# analog_inputs_not_isolated.net
KiCad netlist of a schematic drawn in Altium Designer
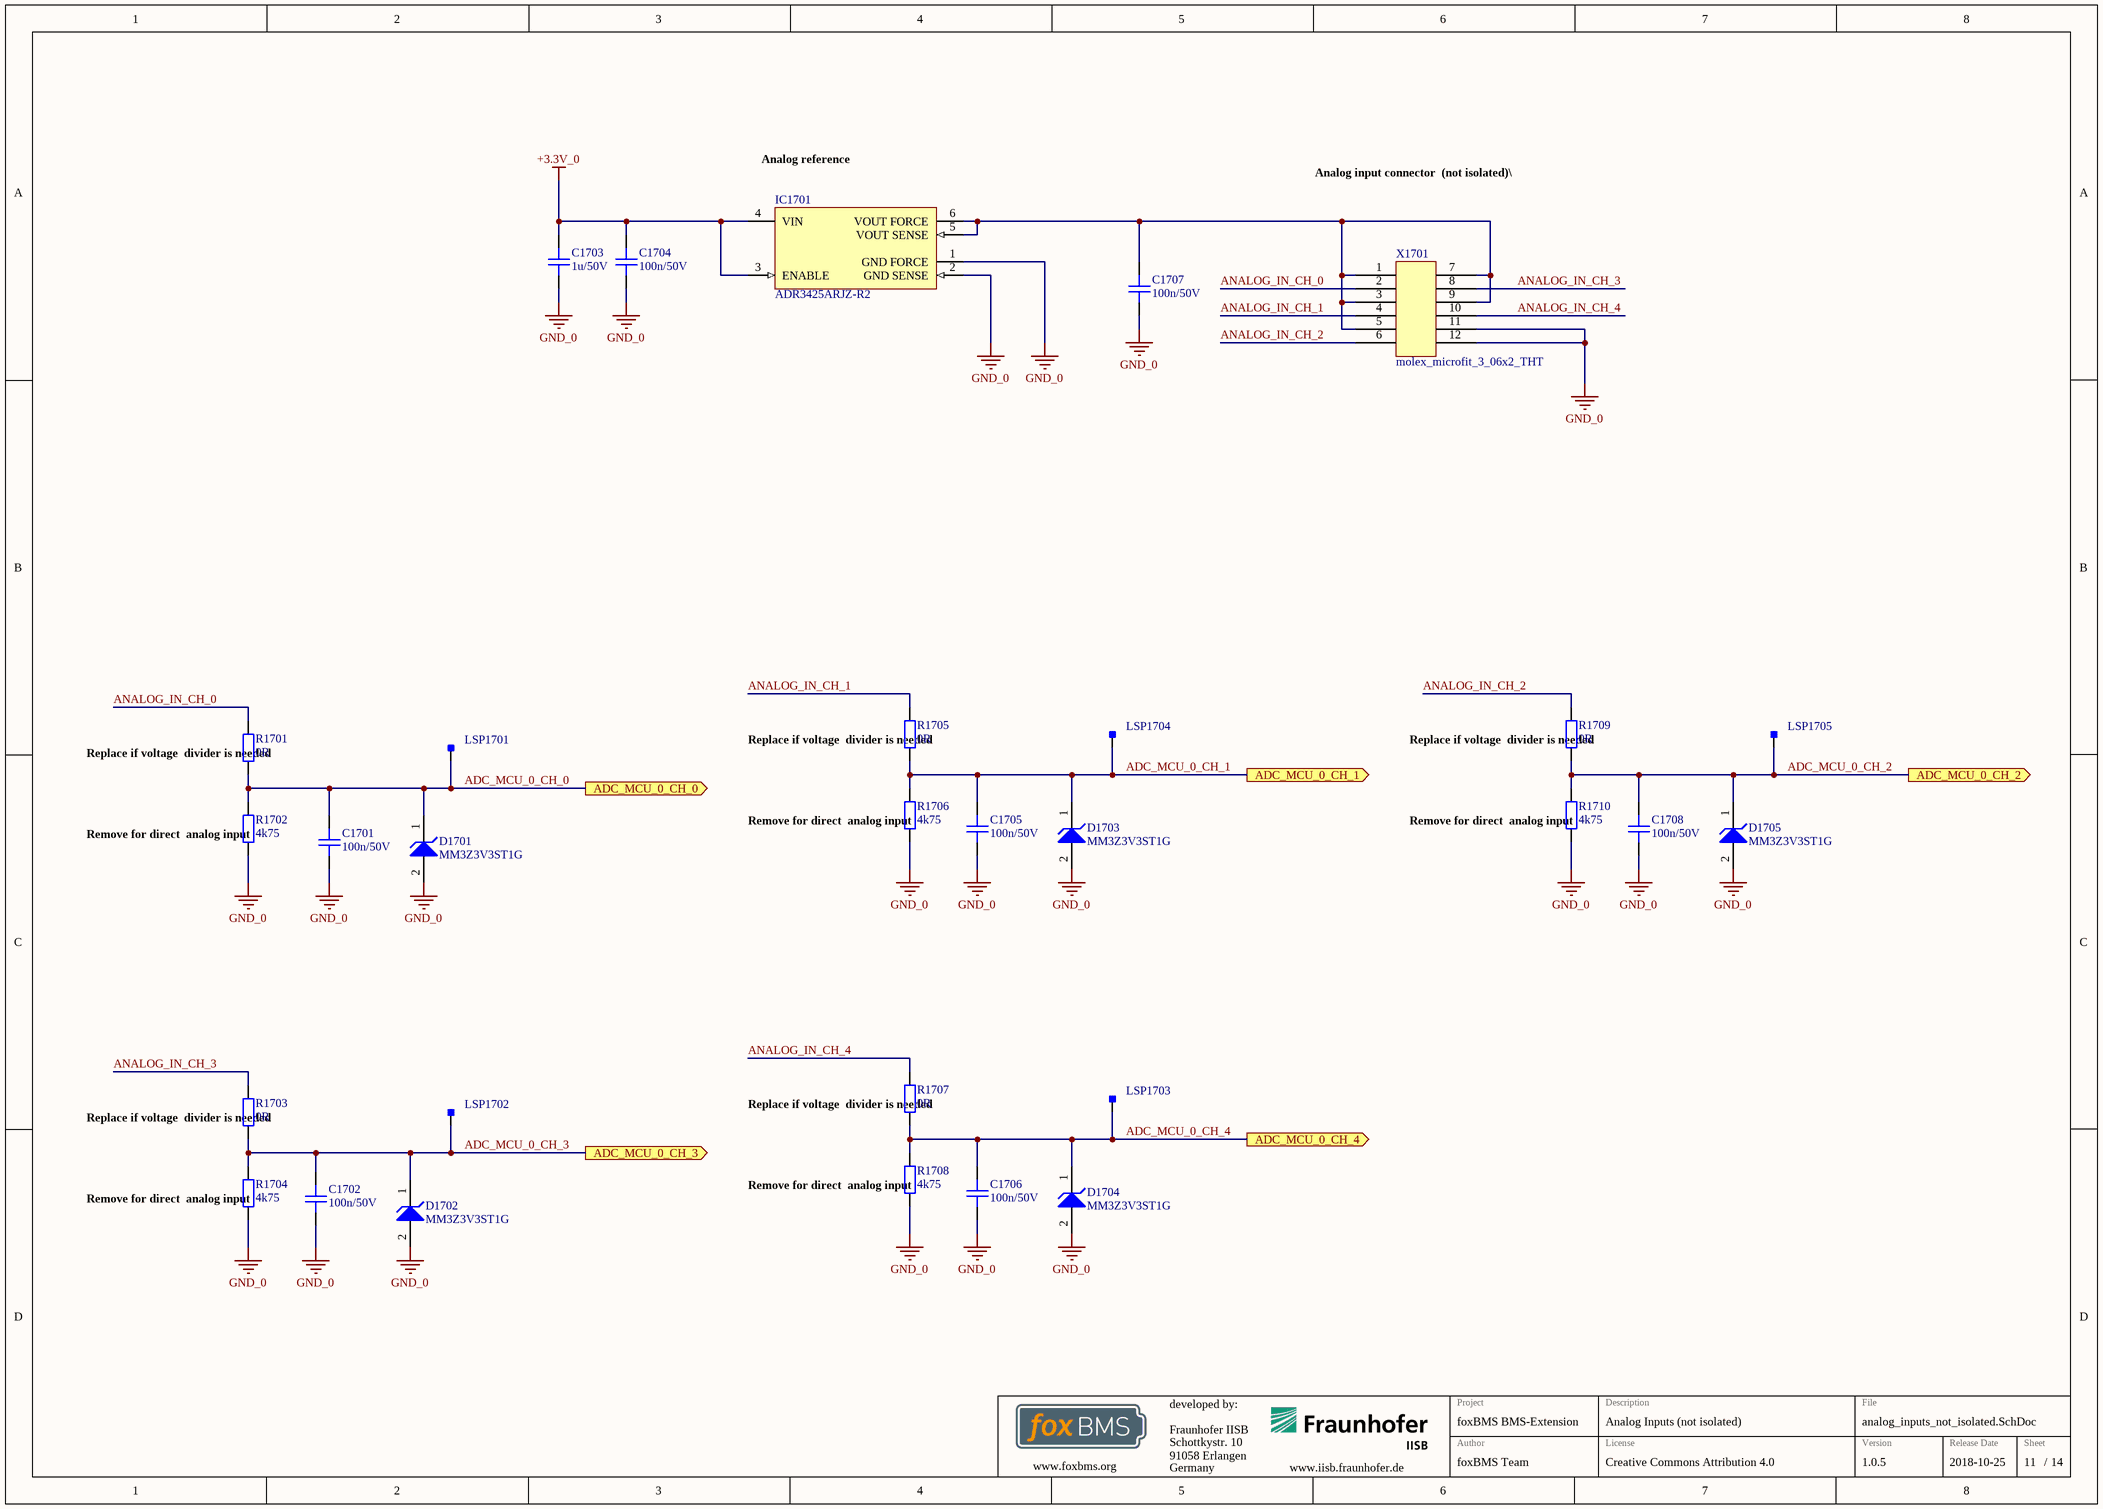
[diagram p0: analog_inputs_not_isolated.SchDoc]

(export (version "E")
  (design (tool "Eeschema 10.0.6"))
  (components
    (comp (ref "C1701")
      (value "100n/50V")
      (footprint "CAPC1608X08N")
      (description "MLCC")
      (fields (field (name "PART NUMBER") "gen_C_ceramic_100n_50V_X7R_0603"))
      (libsource (lib "OE750") (part "C"))
    )
    (comp (ref "C1702")
      (value "100n/50V")
      (footprint "CAPC1608X08N")
      (description "MLCC")
      (fields (field (name "PART NUMBER") "gen_C_ceramic_100n_50V_X7R_0603"))
      (libsource (lib "OE750") (part "C"))
    )
    (comp (ref "C1703")
      (value "1u/50V")
      (footprint "CAPC1608X08N")
      (description "MLCC")
      (fields (field (name "PART NUMBER") "gen_C_ceramic_1u_50V_X7R_0603") (field (name "TOLERANCE") "± 10%"))
      (libsource (lib "OE750") (part "C"))
    )
    (comp (ref "C1704")
      (value "100n/50V")
      (footprint "CAPC1608X08N")
      (description "MLCC")
      (fields (field (name "PART NUMBER") "gen_C_ceramic_100n_50V_X7R_0603"))
      (libsource (lib "OE750") (part "C"))
    )
    (comp (ref "C1705")
      (value "100n/50V")
      (footprint "CAPC1608X08N")
      (description "MLCC")
      (fields (field (name "PART NUMBER") "gen_C_ceramic_100n_50V_X7R_0603"))
      (libsource (lib "OE750") (part "C"))
    )
    (comp (ref "C1706")
      (value "100n/50V")
      (footprint "CAPC1608X08N")
      (description "MLCC")
      (fields (field (name "PART NUMBER") "gen_C_ceramic_100n_50V_X7R_0603"))
      (libsource (lib "OE750") (part "C"))
    )
    (comp (ref "C1707")
      (value "100n/50V")
      (footprint "CAPC1608X08N")
      (description "MLCC")
      (fields (field (name "PART NUMBER") "gen_C_ceramic_100n_50V_X7R_0603"))
      (libsource (lib "OE750") (part "C"))
    )
    (comp (ref "C1708")
      (value "100n/50V")
      (footprint "CAPC1608X08N")
      (description "MLCC")
      (fields (field (name "PART NUMBER") "gen_C_ceramic_100n_50V_X7R_0603"))
      (libsource (lib "OE750") (part "C"))
    )
    (comp (ref "D1701")
      (value "MM3Z3V3ST1G")
      (footprint "ONSC-SOD-323-2-477-02_V")
      (description "Zener Voltage Regulator, 300 mW, Tight Tolerance Portfolio, 2-Pin SOD-323, Pb-Free, Tape and Reel")
      (fields (field (name "MANUFACTURER") "On Semiconductor"))
      (libsource (lib "Altium Content Vault") (part "ONSC-K1A2-2"))
    )
    (comp (ref "D1702")
      (value "MM3Z3V3ST1G")
      (footprint "ONSC-SOD-323-2-477-02_V")
      (description "Zener Voltage Regulator, 300 mW, Tight Tolerance Portfolio, 2-Pin SOD-323, Pb-Free, Tape and Reel")
      (fields (field (name "MANUFACTURER") "On Semiconductor"))
      (libsource (lib "Altium Content Vault") (part "ONSC-K1A2-2"))
    )
    (comp (ref "D1703")
      (value "MM3Z3V3ST1G")
      (footprint "ONSC-SOD-323-2-477-02_V")
      (description "Zener Voltage Regulator, 300 mW, Tight Tolerance Portfolio, 2-Pin SOD-323, Pb-Free, Tape and Reel")
      (fields (field (name "MANUFACTURER") "On Semiconductor"))
      (libsource (lib "Altium Content Vault") (part "ONSC-K1A2-2"))
    )
    (comp (ref "D1704")
      (value "MM3Z3V3ST1G")
      (footprint "ONSC-SOD-323-2-477-02_V")
      (description "Zener Voltage Regulator, 300 mW, Tight Tolerance Portfolio, 2-Pin SOD-323, Pb-Free, Tape and Reel")
      (fields (field (name "MANUFACTURER") "On Semiconductor"))
      (libsource (lib "Altium Content Vault") (part "ONSC-K1A2-2"))
    )
    (comp (ref "D1705")
      (value "MM3Z3V3ST1G")
      (footprint "ONSC-SOD-323-2-477-02_V")
      (description "Zener Voltage Regulator, 300 mW, Tight Tolerance Portfolio, 2-Pin SOD-323, Pb-Free, Tape and Reel")
      (fields (field (name "MANUFACTURER") "On Semiconductor"))
      (libsource (lib "Altium Content Vault") (part "ONSC-K1A2-2"))
    )
    (comp (ref "IC1701")
      (value "ADR3425ARJZ-R2")
      (footprint "ADI-RJ-6_N")
      (fields (field (name "MANUFACTURER") "Analog Devices"))
      (libsource (lib "Altium Content Vault") (part "ADI-ADR34xx-RJ-6"))
    )
    (comp (ref "LSP1701")
      (value "Testpoint_Square")
      (footprint "Testpoint_S1")
      (description "Testpoint, square")
      (libsource (lib "OE750") (part "Testpoint_Square"))
    )
    (comp (ref "LSP1702")
      (value "Testpoint_Square")
      (footprint "Testpoint_S1")
      (description "Testpoint, square")
      (libsource (lib "OE750") (part "Testpoint_Square"))
    )
    (comp (ref "LSP1703")
      (value "Testpoint_Square")
      (footprint "Testpoint_S1")
      (description "Testpoint, square")
      (libsource (lib "OE750") (part "Testpoint_Square"))
    )
    (comp (ref "LSP1704")
      (value "Testpoint_Square")
      (footprint "Testpoint_S1")
      (description "Testpoint, square")
      (libsource (lib "OE750") (part "Testpoint_Square"))
    )
    (comp (ref "LSP1705")
      (value "Testpoint_Square")
      (footprint "Testpoint_S1")
      (description "Testpoint, square")
      (libsource (lib "OE750") (part "Testpoint_Square"))
    )
    (comp (ref "R1701")
      (value "0R")
      (footprint "RESC1608X05N")
      (description "SMD Resistor 0R 0603")
      (fields (field (name "PART NUMBER") "gen_R_0R_0603") (field (name "POWER") "0.1W"))
      (libsource (lib "OE750") (part "R"))
    )
    (comp (ref "R1702")
      (value "4k75")
      (footprint "RESC1608X05N")
      (description "SMD Resistor 4k75 0603")
      (fields (field (name "PART NUMBER") "gen_R_4k75_0603") (field (name "TOLERANCE") "1%"))
      (libsource (lib "OE750") (part "R"))
    )
    (comp (ref "R1703")
      (value "0R")
      (footprint "RESC1608X05N")
      (description "SMD Resistor 0R 0603")
      (fields (field (name "PART NUMBER") "gen_R_0R_0603") (field (name "POWER") "0.1W"))
      (libsource (lib "OE750") (part "R"))
    )
    (comp (ref "R1704")
      (value "4k75")
      (footprint "RESC1608X05N")
      (description "SMD Resistor 4k75 0603")
      (fields (field (name "PART NUMBER") "gen_R_4k75_0603") (field (name "TOLERANCE") "1%"))
      (libsource (lib "OE750") (part "R"))
    )
    (comp (ref "R1705")
      (value "0R")
      (footprint "RESC1608X05N")
      (description "SMD Resistor 0R 0603")
      (fields (field (name "PART NUMBER") "gen_R_0R_0603") (field (name "POWER") "0.1W"))
      (libsource (lib "OE750") (part "R"))
    )
    (comp (ref "R1706")
      (value "4k75")
      (footprint "RESC1608X05N")
      (description "SMD Resistor 4k75 0603")
      (fields (field (name "PART NUMBER") "gen_R_4k75_0603") (field (name "TOLERANCE") "1%"))
      (libsource (lib "OE750") (part "R"))
    )
    (comp (ref "R1707")
      (value "0R")
      (footprint "RESC1608X05N")
      (description "SMD Resistor 0R 0603")
      (fields (field (name "PART NUMBER") "gen_R_0R_0603") (field (name "POWER") "0.1W"))
      (libsource (lib "OE750") (part "R"))
    )
    (comp (ref "R1708")
      (value "4k75")
      (footprint "RESC1608X05N")
      (description "SMD Resistor 4k75 0603")
      (fields (field (name "PART NUMBER") "gen_R_4k75_0603") (field (name "TOLERANCE") "1%"))
      (libsource (lib "OE750") (part "R"))
    )
    (comp (ref "R1709")
      (value "0R")
      (footprint "RESC1608X05N")
      (description "SMD Resistor 0R 0603")
      (fields (field (name "PART NUMBER") "gen_R_0R_0603") (field (name "POWER") "0.1W"))
      (libsource (lib "OE750") (part "R"))
    )
    (comp (ref "R1710")
      (value "4k75")
      (footprint "RESC1608X05N")
      (description "SMD Resistor 4k75 0603")
      (fields (field (name "PART NUMBER") "gen_R_4k75_0603") (field (name "TOLERANCE") "1%"))
      (libsource (lib "OE750") (part "R"))
    )
    (comp (ref "X1701")
      (value "molex_microfit_3_06x2_THT")
      (footprint "43045-1221")
      (fields (field (name "MANUFACTURER") "Molex"))
      (libsource (lib "OE750") (part "X6x2"))
    )
  )
  (nets
    (net (code "1") (name "+3.3V_0") (class "Default")
      (node (ref "C1703") (pin "1") (pinfunction "1_1") (pintype "passive"))
      (node (ref "C1704") (pin "1") (pinfunction "1_1") (pintype "passive"))
      (node (ref "IC1701") (pin "3") (pinfunction "ENABLE_3") (pintype "input"))
      (node (ref "IC1701") (pin "4") (pinfunction "VIN_4") (pintype "power_in"))
    )
    (net (code "2") (name "/ADC_MCU_0_CH_0") (class "Default")
      (node (ref "C1701") (pin "1") (pinfunction "1_1") (pintype "passive"))
      (node (ref "D1701") (pin "1") (pinfunction "K_1") (pintype "passive"))
      (node (ref "LSP1701") (pin "1") (pinfunction "1_1") (pintype "passive"))
      (node (ref "R1701") (pin "2") (pinfunction "2_2") (pintype "passive"))
      (node (ref "R1702") (pin "1") (pinfunction "1_1") (pintype "passive"))
    )
    (net (code "3") (name "/ADC_MCU_0_CH_1") (class "Default")
      (node (ref "C1705") (pin "1") (pinfunction "1_1") (pintype "passive"))
      (node (ref "D1703") (pin "1") (pinfunction "K_1") (pintype "passive"))
      (node (ref "LSP1704") (pin "1") (pinfunction "1_1") (pintype "passive"))
      (node (ref "R1705") (pin "2") (pinfunction "2_2") (pintype "passive"))
      (node (ref "R1706") (pin "1") (pinfunction "1_1") (pintype "passive"))
    )
    (net (code "4") (name "/ADC_MCU_0_CH_2") (class "Default")
      (node (ref "C1708") (pin "1") (pinfunction "1_1") (pintype "passive"))
      (node (ref "D1705") (pin "1") (pinfunction "K_1") (pintype "passive"))
      (node (ref "LSP1705") (pin "1") (pinfunction "1_1") (pintype "passive"))
      (node (ref "R1709") (pin "2") (pinfunction "2_2") (pintype "passive"))
      (node (ref "R1710") (pin "1") (pinfunction "1_1") (pintype "passive"))
    )
    (net (code "5") (name "/ADC_MCU_0_CH_3") (class "Default")
      (node (ref "C1702") (pin "1") (pinfunction "1_1") (pintype "passive"))
      (node (ref "D1702") (pin "1") (pinfunction "K_1") (pintype "passive"))
      (node (ref "LSP1702") (pin "1") (pinfunction "1_1") (pintype "passive"))
      (node (ref "R1703") (pin "2") (pinfunction "2_2") (pintype "passive"))
      (node (ref "R1704") (pin "1") (pinfunction "1_1") (pintype "passive"))
    )
    (net (code "6") (name "/ADC_MCU_0_CH_4") (class "Default")
      (node (ref "C1706") (pin "1") (pinfunction "1_1") (pintype "passive"))
      (node (ref "D1704") (pin "1") (pinfunction "K_1") (pintype "passive"))
      (node (ref "LSP1703") (pin "1") (pinfunction "1_1") (pintype "passive"))
      (node (ref "R1707") (pin "2") (pinfunction "2_2") (pintype "passive"))
      (node (ref "R1708") (pin "1") (pinfunction "1_1") (pintype "passive"))
    )
    (net (code "7") (name "/ANALOG_IN_CH_0") (class "Default")
      (node (ref "R1701") (pin "1") (pinfunction "1_1") (pintype "passive"))
      (node (ref "X1701") (pin "2") (pintype "passive"))
    )
    (net (code "8") (name "/ANALOG_IN_CH_1") (class "Default")
      (node (ref "R1705") (pin "1") (pinfunction "1_1") (pintype "passive"))
      (node (ref "X1701") (pin "4") (pintype "passive"))
    )
    (net (code "9") (name "/ANALOG_IN_CH_2") (class "Default")
      (node (ref "R1709") (pin "1") (pinfunction "1_1") (pintype "passive"))
      (node (ref "X1701") (pin "6") (pintype "passive"))
    )
    (net (code "10") (name "/ANALOG_IN_CH_3") (class "Default")
      (node (ref "R1703") (pin "1") (pinfunction "1_1") (pintype "passive"))
      (node (ref "X1701") (pin "8") (pintype "passive"))
    )
    (net (code "11") (name "/ANALOG_IN_CH_4") (class "Default")
      (node (ref "R1707") (pin "1") (pinfunction "1_1") (pintype "passive"))
      (node (ref "X1701") (pin "10") (pintype "passive"))
    )
    (net (code "12") (name "GND_0") (class "Default")
      (node (ref "C1701") (pin "2") (pinfunction "2_2") (pintype "passive"))
      (node (ref "C1702") (pin "2") (pinfunction "2_2") (pintype "passive"))
      (node (ref "C1703") (pin "2") (pinfunction "2_2") (pintype "passive"))
      (node (ref "C1704") (pin "2") (pinfunction "2_2") (pintype "passive"))
      (node (ref "C1705") (pin "2") (pinfunction "2_2") (pintype "passive"))
      (node (ref "C1706") (pin "2") (pinfunction "2_2") (pintype "passive"))
      (node (ref "C1707") (pin "2") (pinfunction "2_2") (pintype "passive"))
      (node (ref "C1708") (pin "2") (pinfunction "2_2") (pintype "passive"))
      (node (ref "D1701") (pin "2") (pinfunction "A_2") (pintype "passive"))
      (node (ref "D1702") (pin "2") (pinfunction "A_2") (pintype "passive"))
      (node (ref "D1703") (pin "2") (pinfunction "A_2") (pintype "passive"))
      (node (ref "D1704") (pin "2") (pinfunction "A_2") (pintype "passive"))
      (node (ref "D1705") (pin "2") (pinfunction "A_2") (pintype "passive"))
      (node (ref "IC1701") (pin "1") (pinfunction "GND_FORCE_1") (pintype "power_in"))
      (node (ref "IC1701") (pin "2") (pinfunction "GND_SENSE_2") (pintype "input"))
      (node (ref "R1702") (pin "2") (pinfunction "2_2") (pintype "passive"))
      (node (ref "R1704") (pin "2") (pinfunction "2_2") (pintype "passive"))
      (node (ref "R1706") (pin "2") (pinfunction "2_2") (pintype "passive"))
      (node (ref "R1708") (pin "2") (pinfunction "2_2") (pintype "passive"))
      (node (ref "R1710") (pin "2") (pinfunction "2_2") (pintype "passive"))
      (node (ref "X1701") (pin "11") (pintype "passive"))
      (node (ref "X1701") (pin "12") (pintype "passive"))
    )
    (net (code "13") (name "Net-(IC1701-VOUT_FORCE)") (class "Default")
      (node (ref "C1707") (pin "1") (pinfunction "1_1") (pintype "passive"))
      (node (ref "IC1701") (pin "5") (pinfunction "VOUT_SENSE_5") (pintype "input"))
      (node (ref "IC1701") (pin "6") (pinfunction "VOUT_FORCE_6") (pintype "power_in"))
      (node (ref "X1701") (pin "1") (pintype "passive"))
      (node (ref "X1701") (pin "3") (pintype "passive"))
      (node (ref "X1701") (pin "5") (pintype "passive"))
      (node (ref "X1701") (pin "7") (pintype "passive"))
      (node (ref "X1701") (pin "9") (pintype "passive"))
    )
  )
)
